# PSD_Mount_v16.net
KiCad netlist of a schematic drawn in EAGLE
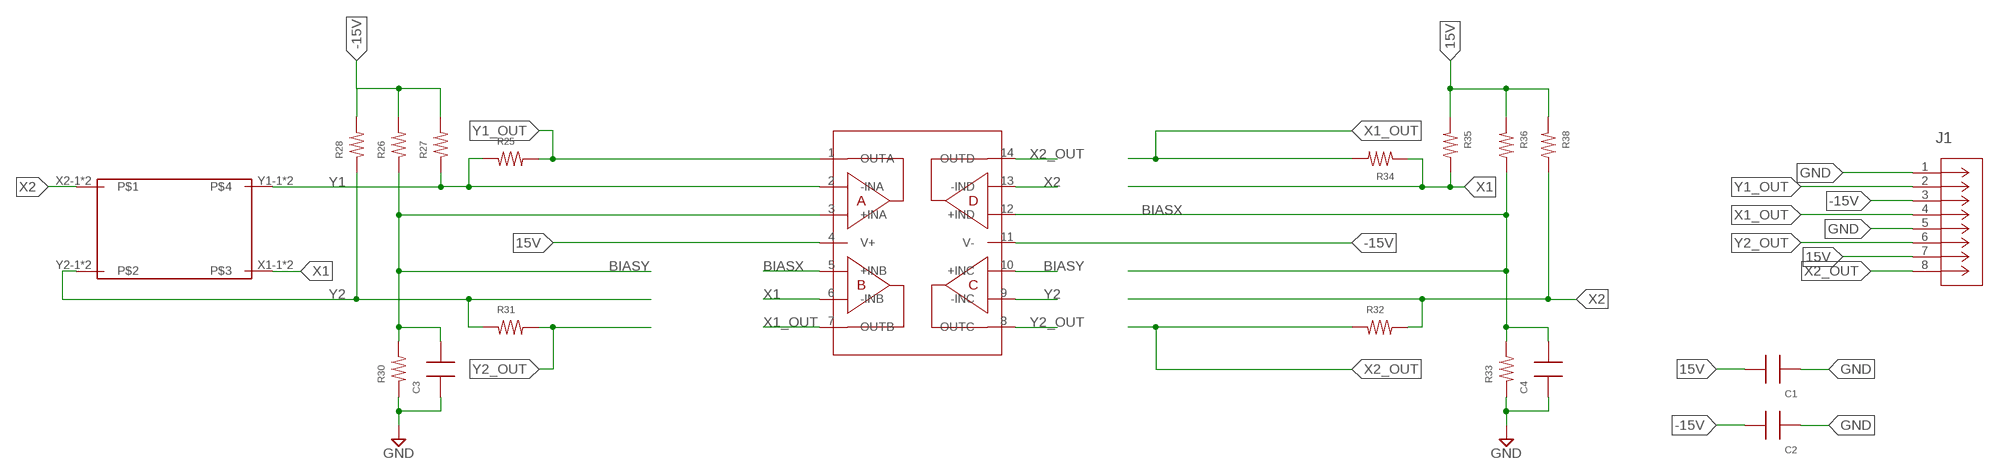
[diagram p0: schematic, sheet 1]

(export (version "E")
  (design (tool "Eeschema 10.0.6"))
  (components
    (comp (ref "AMP1")
      (value "OPA4140")
      (footprint "eagle-import:SOP65P640X120-14N")
      (libsource (lib "eagle-import") (part "OPA4140"))
    )
    (comp (ref "C1")
      (value "CAP0603")
      (footprint "eagle-import:0603")
      (libsource (lib "eagle-import") (part "CAP0603"))
    )
    (comp (ref "C2")
      (value "CAP0603")
      (footprint "eagle-import:0603")
      (libsource (lib "eagle-import") (part "CAP0603"))
    )
    (comp (ref "C3")
      (value "CAP0603")
      (footprint "eagle-import:0603")
      (libsource (lib "eagle-import") (part "CAP0603"))
    )
    (comp (ref "C4")
      (value "CAP0603")
      (footprint "eagle-import:0603")
      (libsource (lib "eagle-import") (part "CAP0603"))
    )
    (comp (ref "J1")
      (value "75869-332LF")
      (footprint "eagle-import:CONN_332LF_AMP")
      (fields (field (name "COPYRIGHT") "Copyright (C) 2018 Accelerated Designs. All rights reserved"))
      (libsource (lib "eagle-import") (part "75869-332LF"))
    )
    (comp (ref "R25")
      (value "RES0603")
      (footprint "eagle-import:0603")
      (libsource (lib "eagle-import") (part "RES0603"))
    )
    (comp (ref "R26")
      (value "RES0603")
      (footprint "eagle-import:0603")
      (libsource (lib "eagle-import") (part "RES0603"))
    )
    (comp (ref "R27")
      (value "RES0603")
      (footprint "eagle-import:0603")
      (libsource (lib "eagle-import") (part "RES0603"))
    )
    (comp (ref "R28")
      (value "RES0603")
      (footprint "eagle-import:0603")
      (libsource (lib "eagle-import") (part "RES0603"))
    )
    (comp (ref "R30")
      (value "RES0603")
      (footprint "eagle-import:0603")
      (libsource (lib "eagle-import") (part "RES0603"))
    )
    (comp (ref "R31")
      (value "RES0603")
      (footprint "eagle-import:0603")
      (libsource (lib "eagle-import") (part "RES0603"))
    )
    (comp (ref "R32")
      (value "RES0603")
      (footprint "eagle-import:0603")
      (libsource (lib "eagle-import") (part "RES0603"))
    )
    (comp (ref "R33")
      (value "RES0603")
      (footprint "eagle-import:0603")
      (libsource (lib "eagle-import") (part "RES0603"))
    )
    (comp (ref "R34")
      (value "RES0603")
      (footprint "eagle-import:0603")
      (libsource (lib "eagle-import") (part "RES0603"))
    )
    (comp (ref "R35")
      (value "RES0603")
      (footprint "eagle-import:0603")
      (libsource (lib "eagle-import") (part "RES0603"))
    )
    (comp (ref "R36")
      (value "RES0603")
      (footprint "eagle-import:0603")
      (libsource (lib "eagle-import") (part "RES0603"))
    )
    (comp (ref "R38")
      (value "RES0603")
      (footprint "eagle-import:0603")
      (libsource (lib "eagle-import") (part "RES0603"))
    )
    (comp (ref "U$1")
      (value "2L10UV_SU7")
      (footprint "eagle-import:2L10UV_SU7")
      (libsource (lib "eagle-import") (part "2L10UV_SU7"))
    )
  )
  (nets
    (net (code "1") (name "-15V") (class "Default")
      (node (ref "AMP1") (pin "11") (pinfunction "V-_11") (pintype "bidirectional"))
      (node (ref "C2") (pin "2") (pinfunction "P$2_2") (pintype "passive"))
      (node (ref "J1") (pin "3") (pinfunction "3_3") (pintype "passive"))
      (node (ref "R26") (pin "2") (pinfunction "P$2_2") (pintype "passive"))
      (node (ref "R27") (pin "2") (pinfunction "P$2_2") (pintype "passive"))
      (node (ref "R28") (pin "2") (pinfunction "P$2_2") (pintype "passive"))
    )
    (net (code "2") (name "/BIASX") (class "Default")
      (node (ref "AMP1") (pin "12") (pinfunction "+IND_12") (pintype "bidirectional"))
      (node (ref "AMP1") (pin "5") (pinfunction "+INB_5") (pintype "bidirectional"))
      (node (ref "C4") (pin "2") (pinfunction "P$2_2") (pintype "passive"))
      (node (ref "R33") (pin "2") (pinfunction "P$2_2") (pintype "passive"))
      (node (ref "R36") (pin "2") (pinfunction "P$2_2") (pintype "passive"))
    )
    (net (code "3") (name "/BIASY") (class "Default")
      (node (ref "AMP1") (pin "10") (pinfunction "+INC_10") (pintype "bidirectional"))
      (node (ref "AMP1") (pin "3") (pinfunction "+INA_3") (pintype "bidirectional"))
      (node (ref "C3") (pin "2") (pinfunction "P$2_2") (pintype "passive"))
      (node (ref "R26") (pin "1") (pinfunction "P$1_1") (pintype "passive"))
      (node (ref "R30") (pin "2") (pinfunction "P$2_2") (pintype "passive"))
    )
    (net (code "4") (name "/Y1") (class "Default")
      (node (ref "AMP1") (pin "2") (pinfunction "-INA_2") (pintype "bidirectional"))
      (node (ref "R25") (pin "1") (pinfunction "P$1_1") (pintype "passive"))
      (node (ref "R27") (pin "1") (pinfunction "P$1_1") (pintype "passive"))
      (node (ref "U$1") (pin "Y1-1") (pinfunction "P$4_Y1-1") (pintype "bidirectional"))
      (node (ref "U$1") (pin "Y1-2") (pinfunction "P$4_Y1-2") (pintype "bidirectional"))
    )
    (net (code "5") (name "/Y2") (class "Default")
      (node (ref "AMP1") (pin "9") (pinfunction "-INC_9") (pintype "bidirectional"))
      (node (ref "R28") (pin "1") (pinfunction "P$1_1") (pintype "passive"))
      (node (ref "R31") (pin "1") (pinfunction "P$1_1") (pintype "passive"))
      (node (ref "U$1") (pin "Y2-1") (pinfunction "P$2_Y2-1") (pintype "bidirectional"))
      (node (ref "U$1") (pin "Y2-2") (pinfunction "P$2_Y2-2") (pintype "bidirectional"))
    )
    (net (code "6") (name "15V") (class "Default")
      (node (ref "AMP1") (pin "4") (pinfunction "V+_4") (pintype "bidirectional"))
      (node (ref "C1") (pin "2") (pinfunction "P$2_2") (pintype "passive"))
      (node (ref "J1") (pin "7") (pinfunction "7_7") (pintype "passive"))
      (node (ref "R35") (pin "1") (pinfunction "P$1_1") (pintype "passive"))
      (node (ref "R36") (pin "1") (pinfunction "P$1_1") (pintype "passive"))
      (node (ref "R38") (pin "1") (pinfunction "P$1_1") (pintype "passive"))
    )
    (net (code "7") (name "GND") (class "Default")
      (node (ref "C1") (pin "1") (pinfunction "P$1_1") (pintype "passive"))
      (node (ref "C2") (pin "1") (pinfunction "P$1_1") (pintype "passive"))
      (node (ref "C3") (pin "1") (pinfunction "P$1_1") (pintype "passive"))
      (node (ref "C4") (pin "1") (pinfunction "P$1_1") (pintype "passive"))
      (node (ref "J1") (pin "1") (pinfunction "1_1") (pintype "passive"))
      (node (ref "J1") (pin "5") (pinfunction "5_5") (pintype "passive"))
      (node (ref "R30") (pin "1") (pinfunction "P$1_1") (pintype "passive"))
      (node (ref "R33") (pin "1") (pinfunction "P$1_1") (pintype "passive"))
    )
    (net (code "8") (name "X1") (class "Default")
      (node (ref "AMP1") (pin "6") (pinfunction "-INB_6") (pintype "bidirectional"))
      (node (ref "R34") (pin "1") (pinfunction "P$1_1") (pintype "passive"))
      (node (ref "R35") (pin "2") (pinfunction "P$2_2") (pintype "passive"))
      (node (ref "U$1") (pin "X1-1") (pinfunction "P$3_X1-1") (pintype "bidirectional"))
      (node (ref "U$1") (pin "X1-2") (pinfunction "P$3_X1-2") (pintype "bidirectional"))
    )
    (net (code "9") (name "X1_OUT") (class "Default")
      (node (ref "AMP1") (pin "7") (pinfunction "OUTB_7") (pintype "bidirectional"))
      (node (ref "J1") (pin "4") (pinfunction "4_4") (pintype "passive"))
      (node (ref "R34") (pin "2") (pinfunction "P$2_2") (pintype "passive"))
    )
    (net (code "10") (name "X2") (class "Default")
      (node (ref "AMP1") (pin "13") (pinfunction "-IND_13") (pintype "bidirectional"))
      (node (ref "R32") (pin "2") (pinfunction "P$2_2") (pintype "passive"))
      (node (ref "R38") (pin "2") (pinfunction "P$2_2") (pintype "passive"))
      (node (ref "U$1") (pin "X2-1") (pinfunction "P$1_X2-1") (pintype "bidirectional"))
      (node (ref "U$1") (pin "X2-2") (pinfunction "P$1_X2-2") (pintype "bidirectional"))
    )
    (net (code "11") (name "X2_OUT") (class "Default")
      (node (ref "AMP1") (pin "14") (pinfunction "OUTD_14") (pintype "bidirectional"))
      (node (ref "J1") (pin "8") (pinfunction "8_8") (pintype "passive"))
      (node (ref "R32") (pin "1") (pinfunction "P$1_1") (pintype "passive"))
    )
    (net (code "12") (name "Y1_OUT") (class "Default")
      (node (ref "AMP1") (pin "1") (pinfunction "OUTA_1") (pintype "bidirectional"))
      (node (ref "J1") (pin "2") (pinfunction "2_2") (pintype "passive"))
      (node (ref "R25") (pin "2") (pinfunction "P$2_2") (pintype "passive"))
    )
    (net (code "13") (name "Y2_OUT") (class "Default")
      (node (ref "AMP1") (pin "8") (pinfunction "OUTC_8") (pintype "bidirectional"))
      (node (ref "J1") (pin "6") (pinfunction "6_6") (pintype "passive"))
      (node (ref "R31") (pin "2") (pinfunction "P$2_2") (pintype "passive"))
    )
  )
)
